# generic_victim.net
KiCad netlist of a schematic drawn in EAGLE
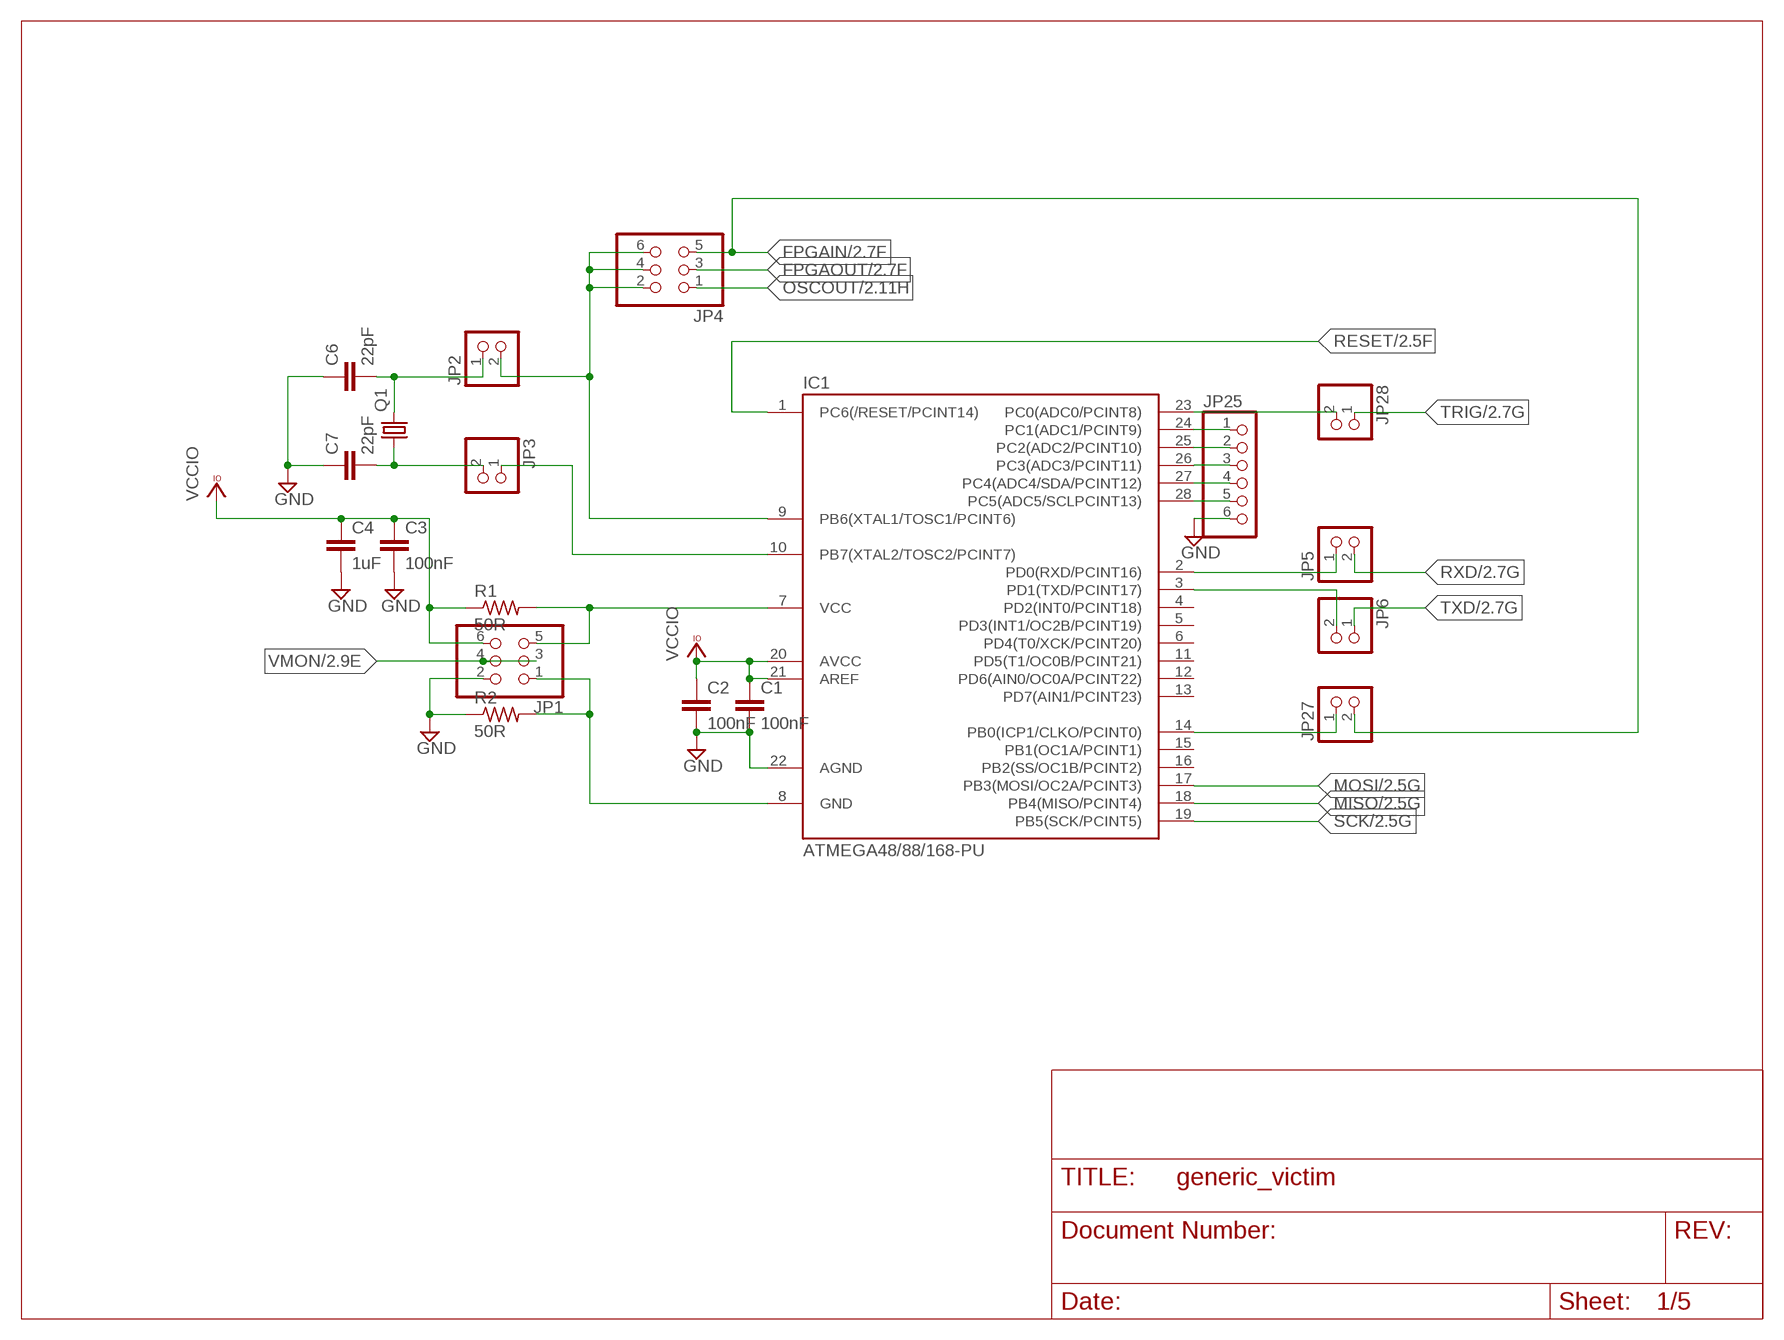
[diagram p0: schematic, sheet 1]
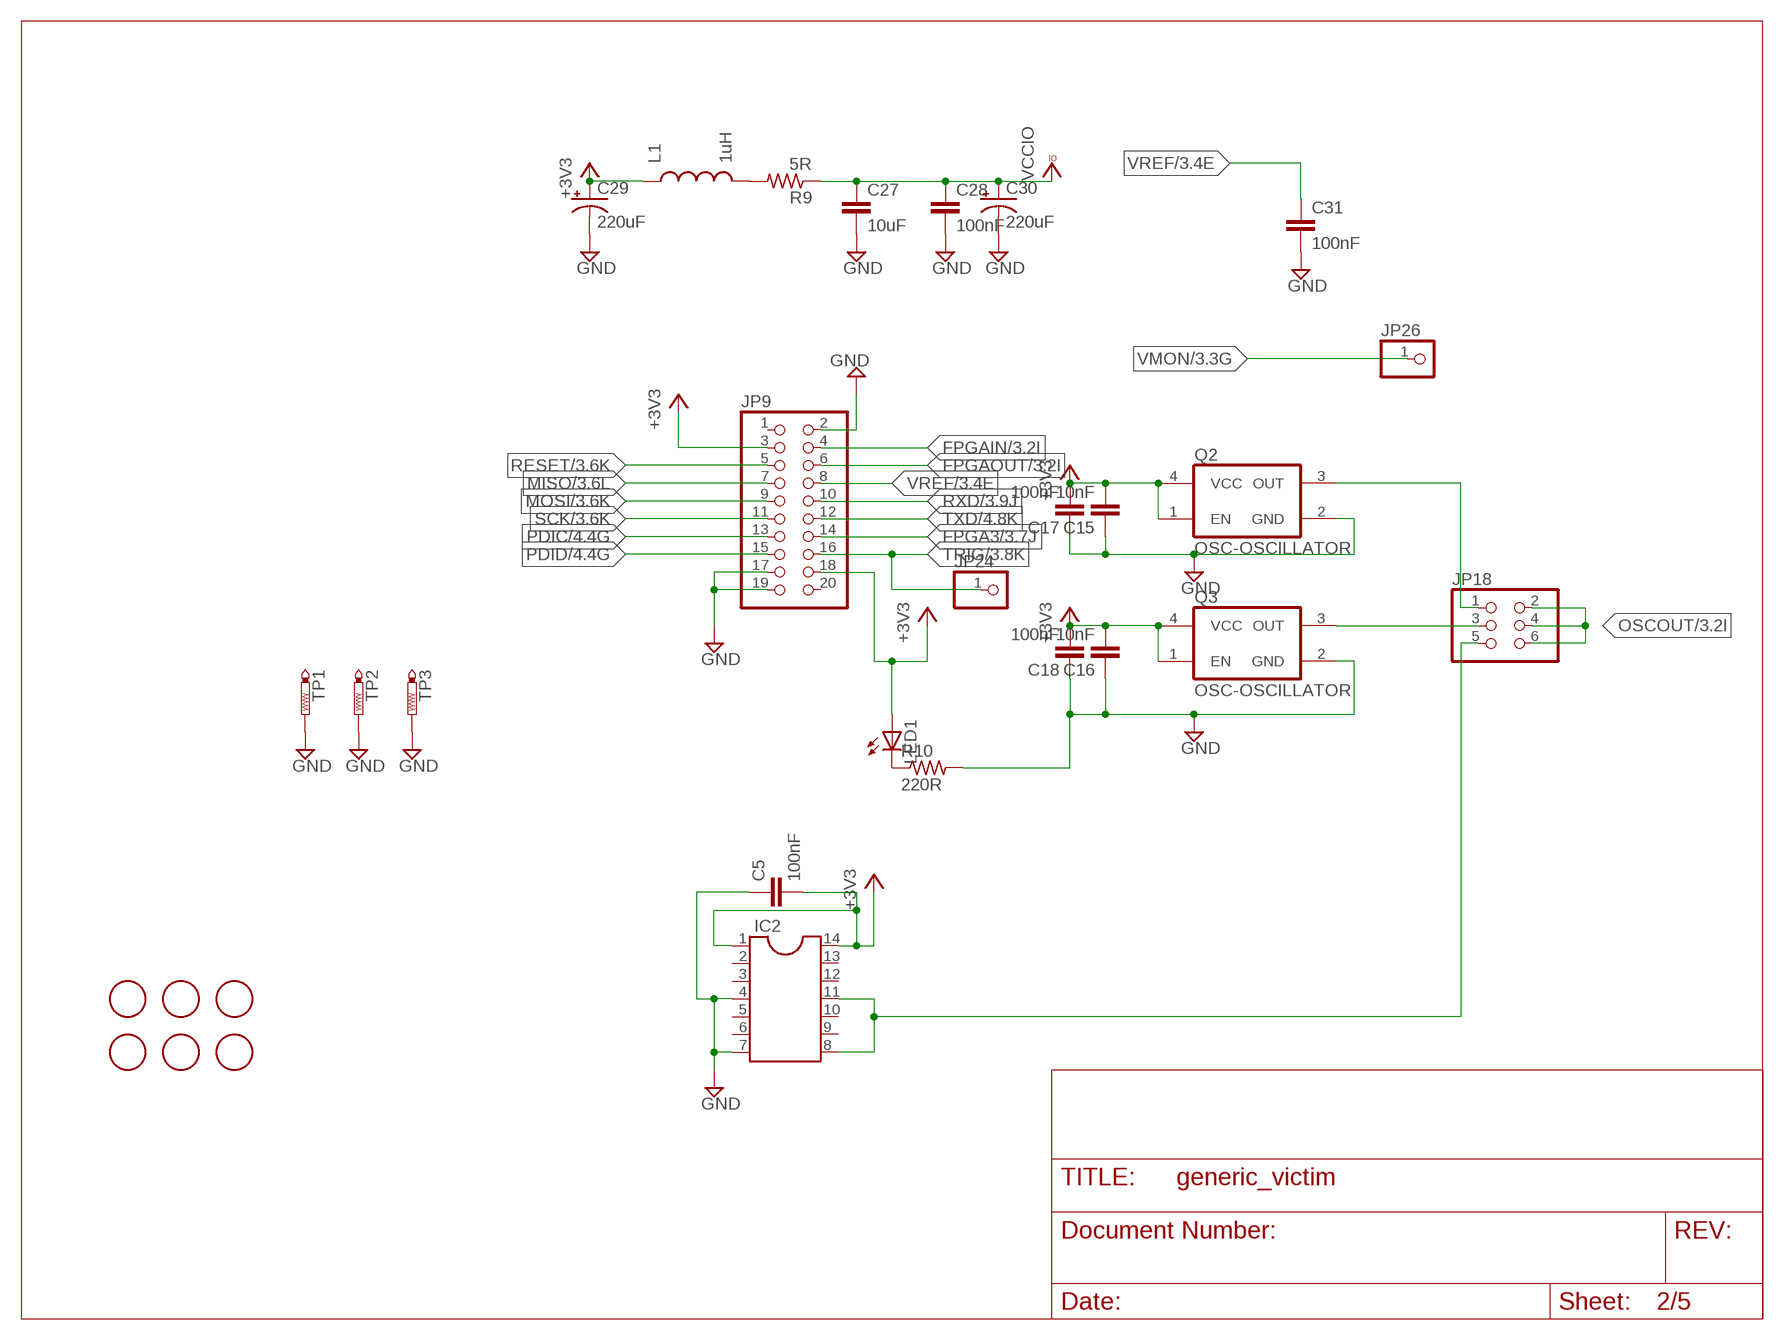
[diagram p1: schematic, sheet 2]
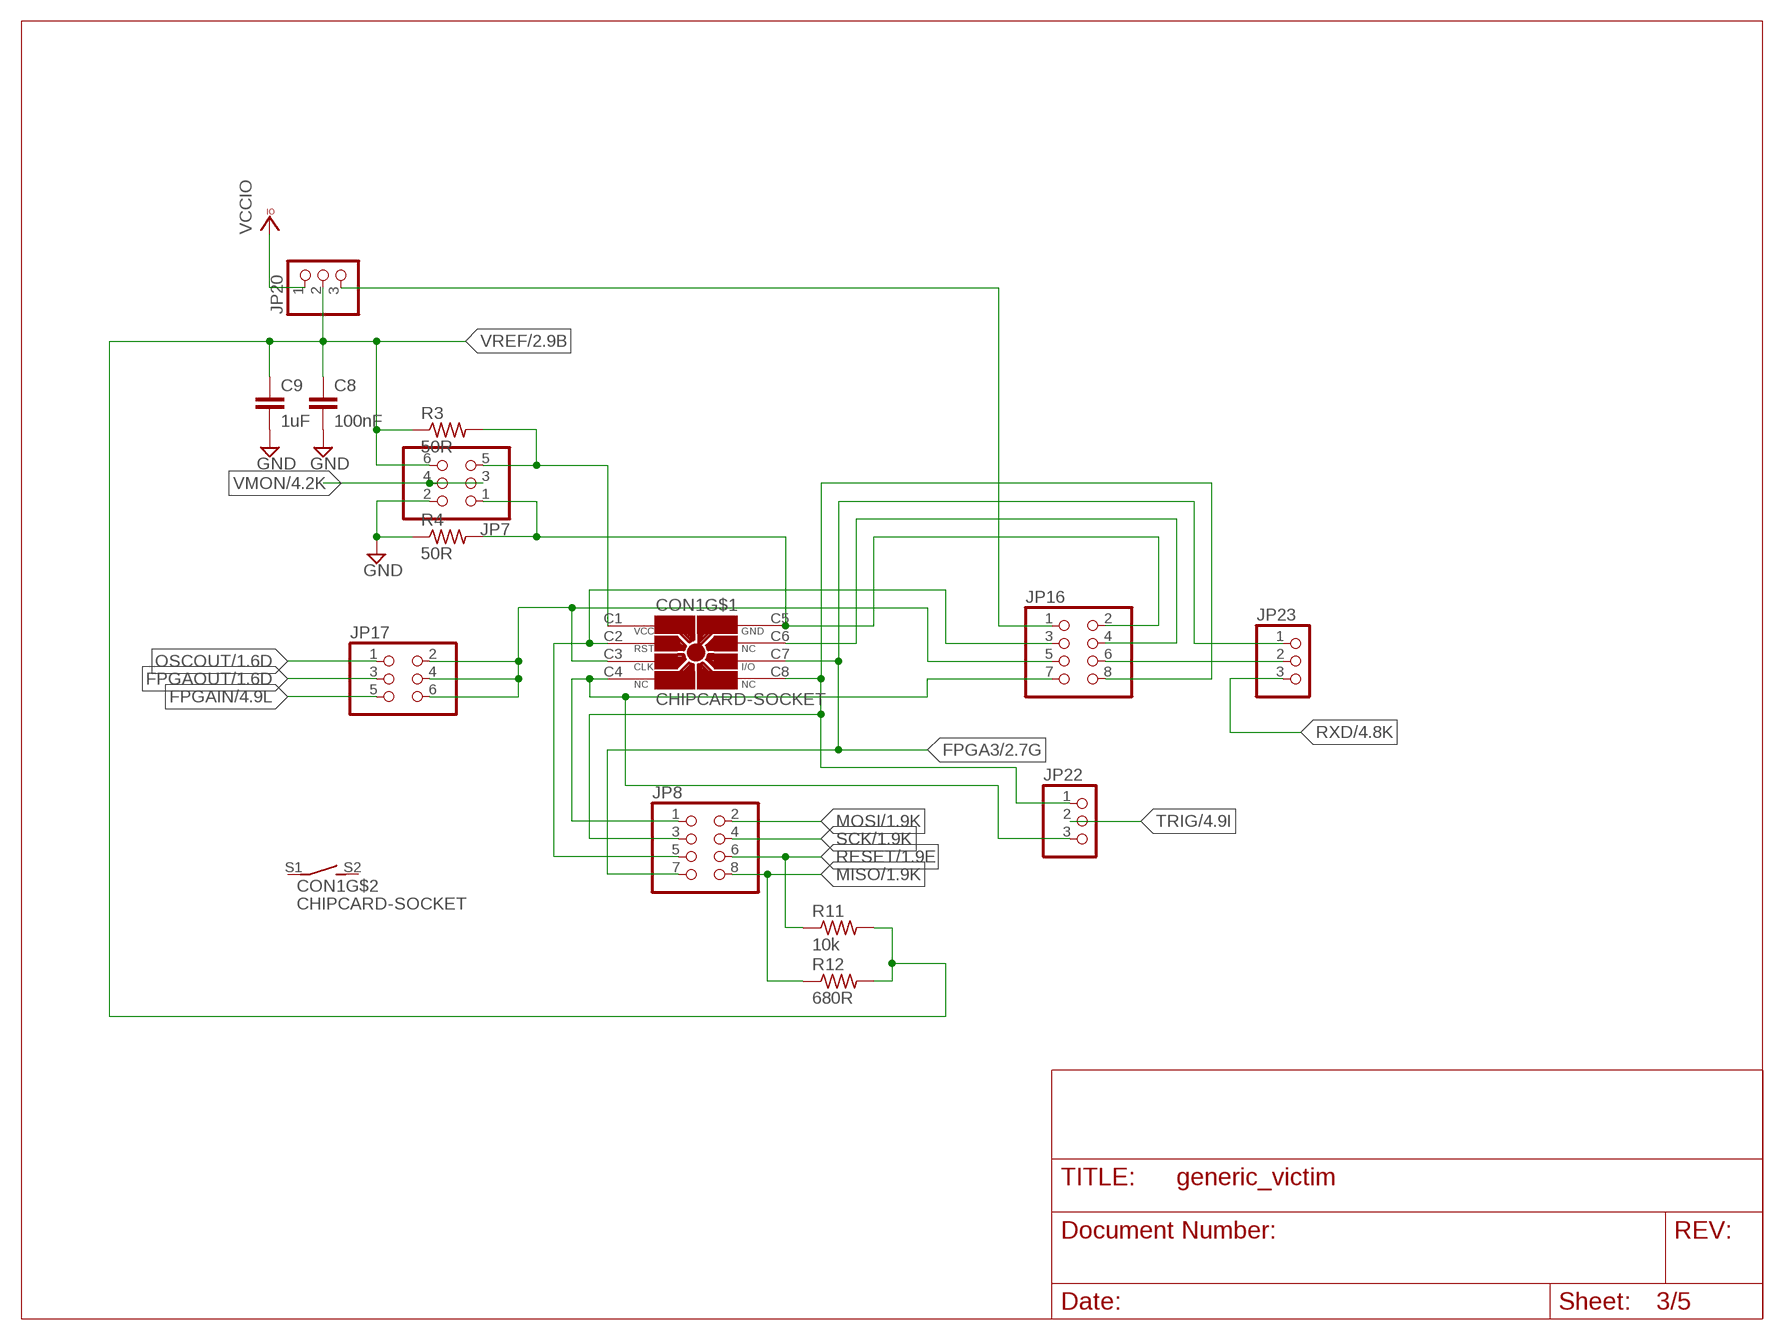
[diagram p2: schematic, sheet 3]
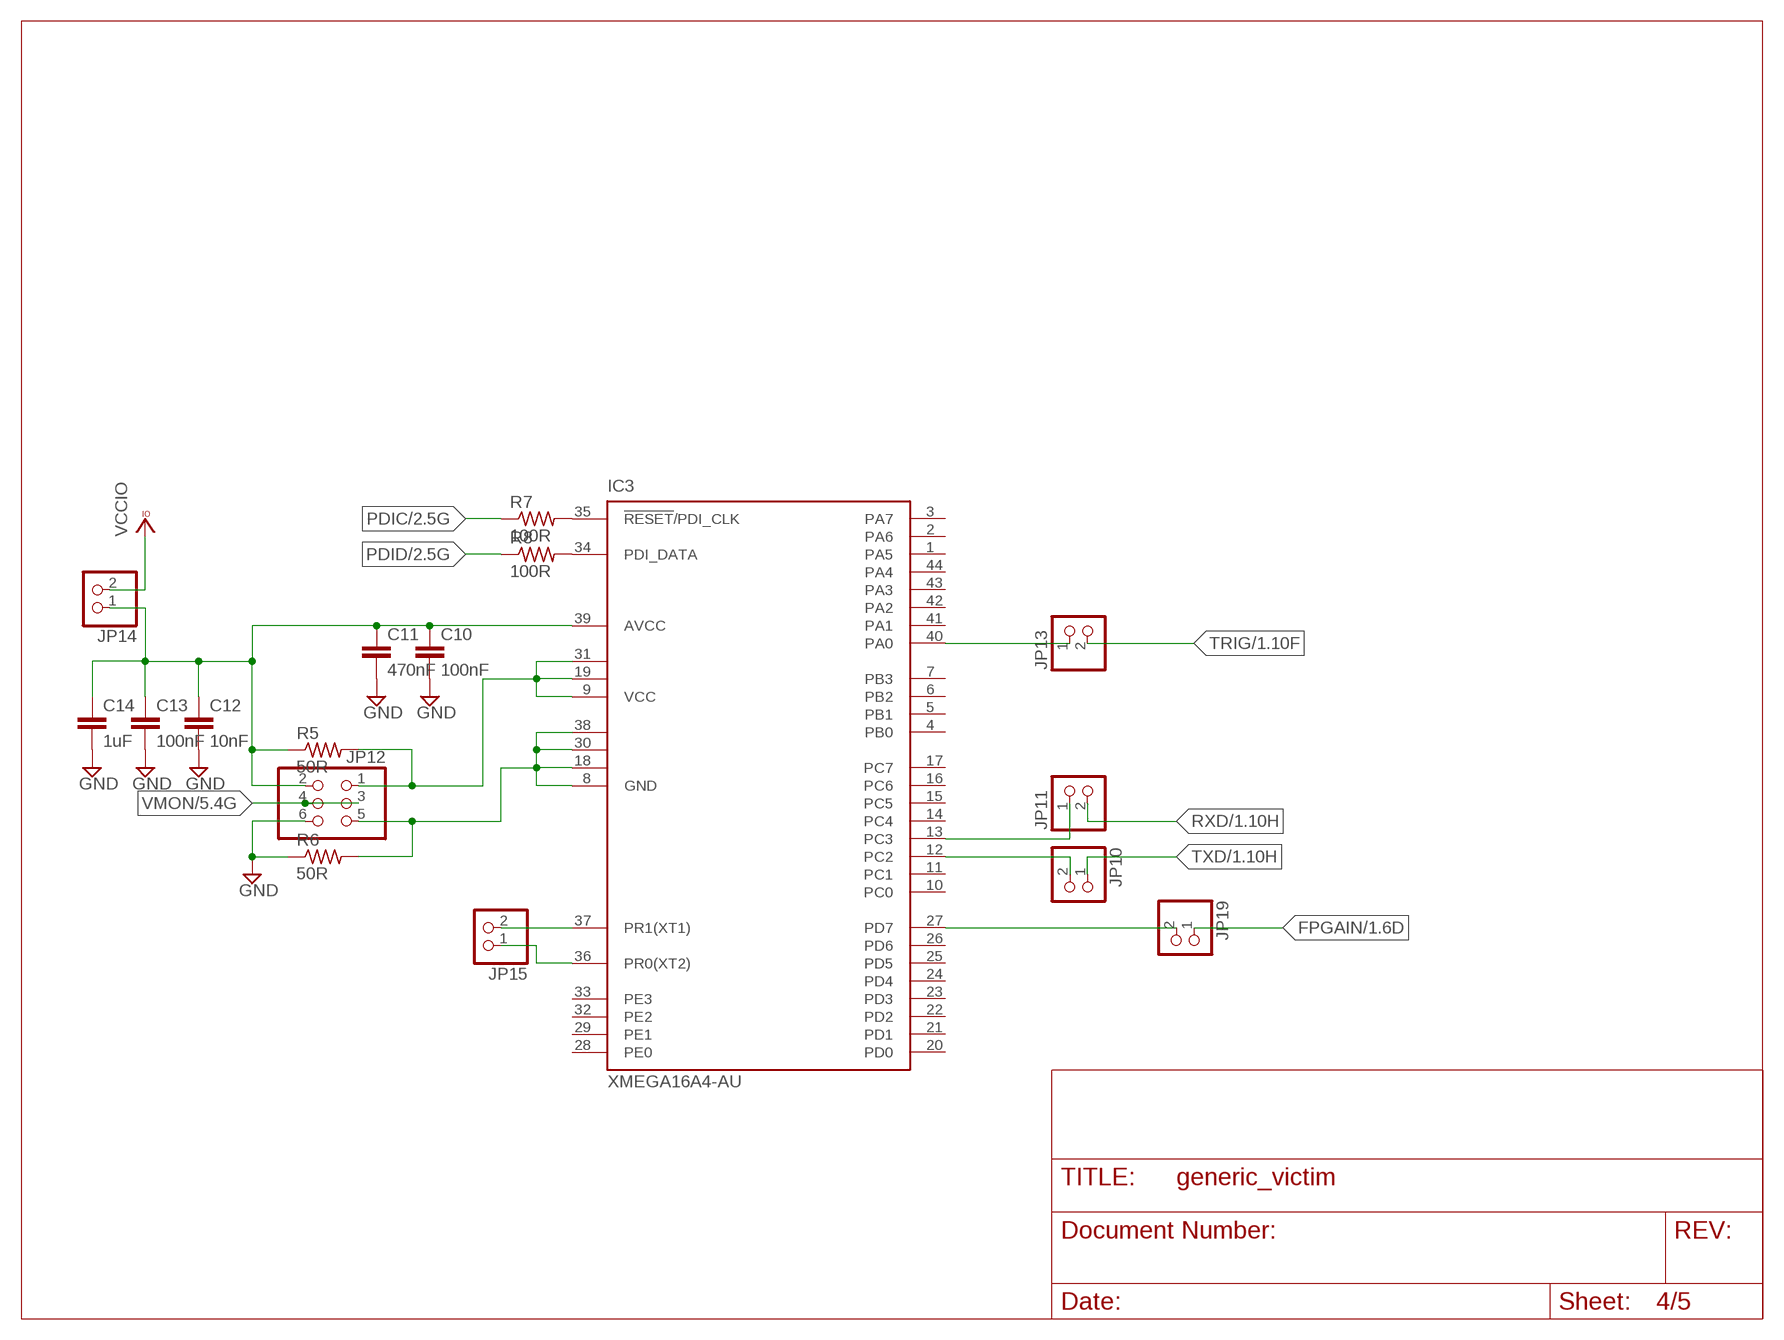
[diagram p3: schematic, sheet 4]
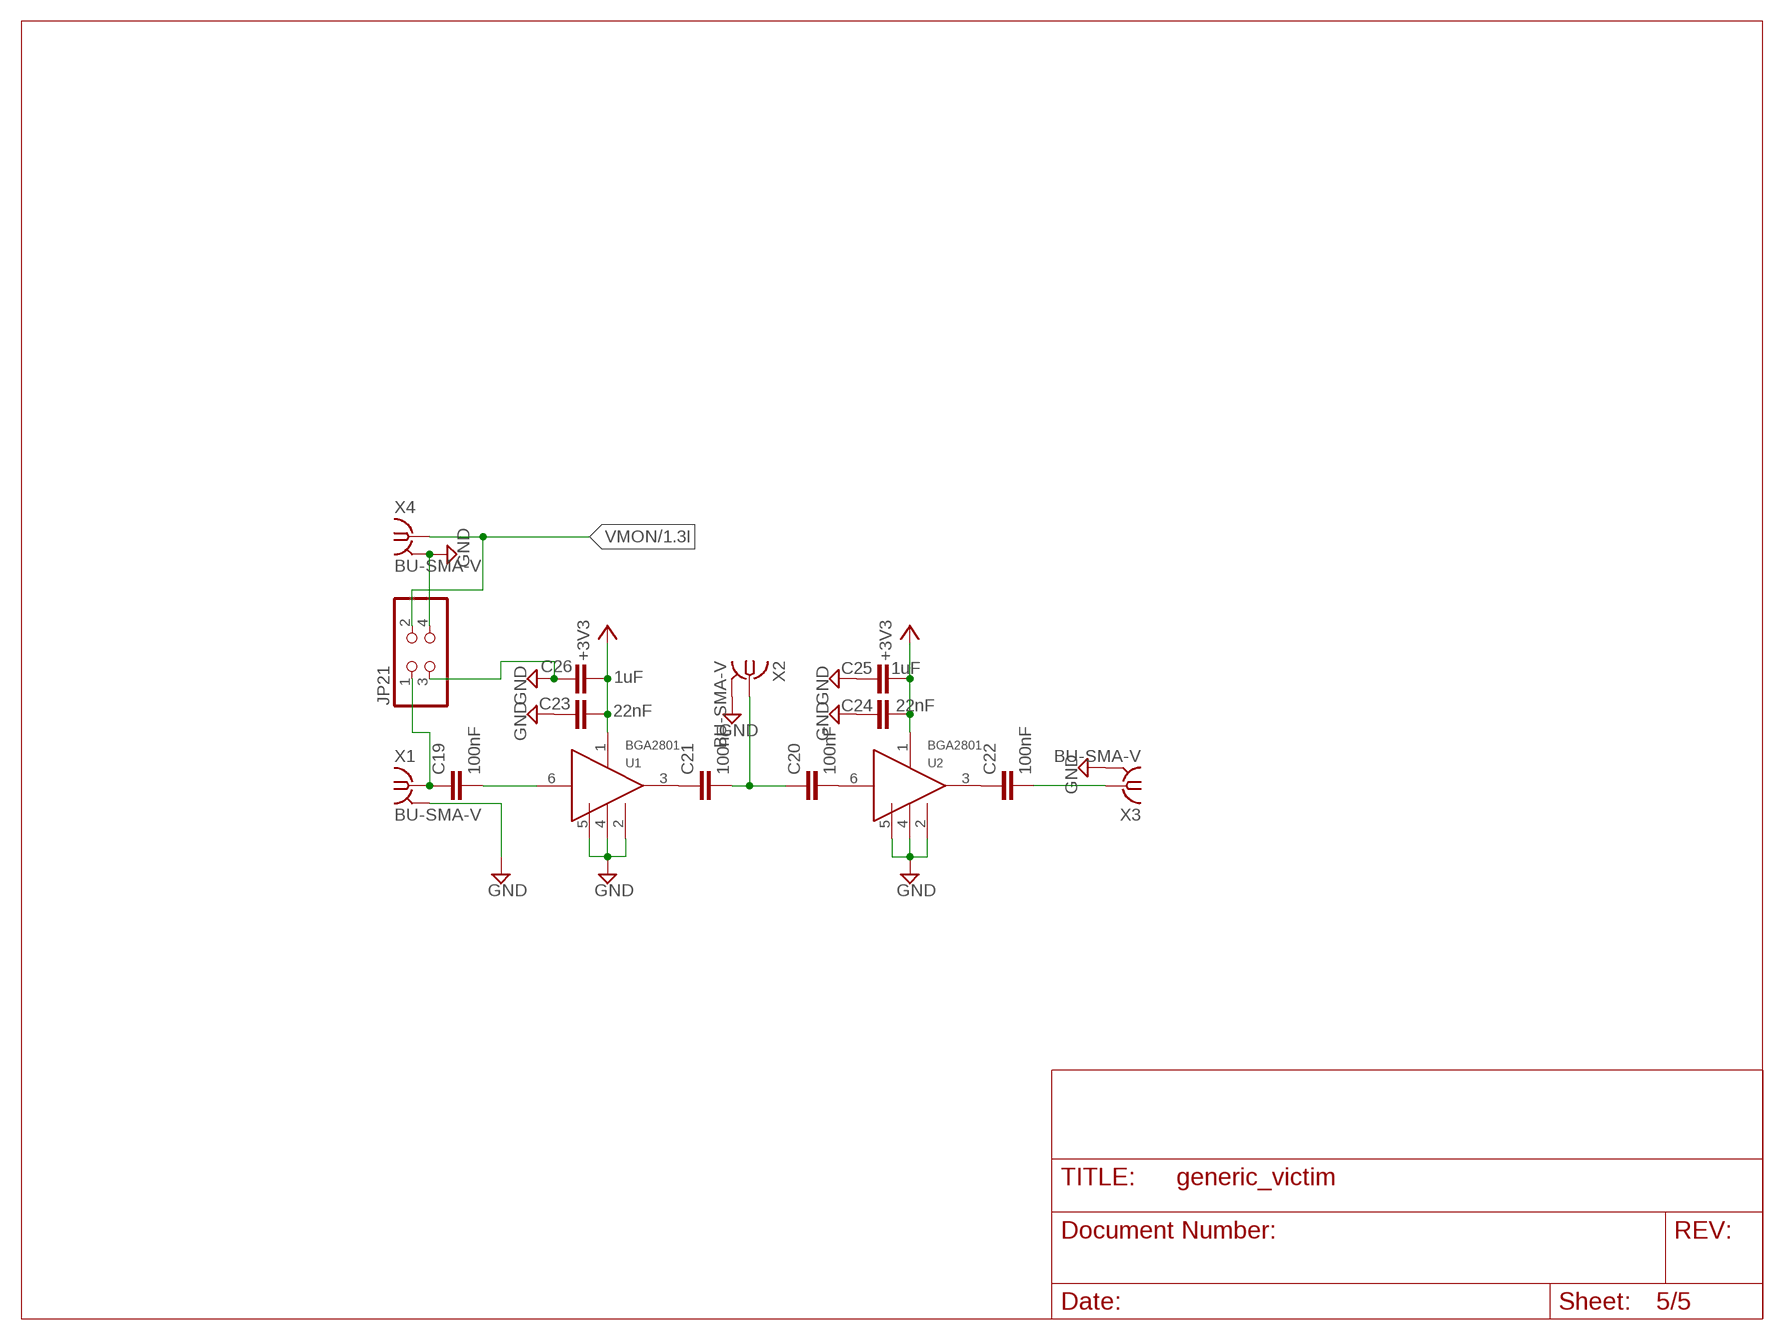
[diagram p4: schematic, sheet 5]

(export (version "E")
  (design (tool "Eeschema 10.0.6"))
  (components
    (comp (ref "C10")
      (value "100nF")
      (footprint "eagle-import:C0805")
      (libsource (lib "eagle-import") (part "resistor_C-EUC0805"))
    )
    (comp (ref "C11")
      (value "470nF")
      (footprint "eagle-import:C0805")
      (libsource (lib "eagle-import") (part "resistor_C-EUC0805"))
    )
    (comp (ref "C12")
      (value "10nF")
      (footprint "eagle-import:C0805")
      (libsource (lib "eagle-import") (part "resistor_C-EUC0805"))
    )
    (comp (ref "C13")
      (value "100nF")
      (footprint "eagle-import:C0805")
      (libsource (lib "eagle-import") (part "resistor_C-EUC0805"))
    )
    (comp (ref "C14")
      (value "1uF")
      (footprint "eagle-import:C0805")
      (libsource (lib "eagle-import") (part "resistor_C-EUC0805"))
    )
    (comp (ref "IC3")
      (value "XMEGA16A4-AU")
      (footprint "eagle-import:TQFP44")
      (libsource (lib "eagle-import") (part "XMEGA16A4A"))
    )
    (comp (ref "JP10")
      (value "PINHD-1X2")
      (footprint "eagle-import:1X02")
      (libsource (lib "eagle-import") (part "PINHD-1X2"))
    )
    (comp (ref "JP11")
      (value "PINHD-1X2")
      (footprint "eagle-import:1X02")
      (libsource (lib "eagle-import") (part "PINHD-1X2"))
    )
    (comp (ref "JP12")
      (value "PINHD-2X3")
      (footprint "eagle-import:2X03")
      (libsource (lib "eagle-import") (part "PINHD-2X3"))
    )
    (comp (ref "JP13")
      (value "PINHD-1X2")
      (footprint "eagle-import:1X02")
      (libsource (lib "eagle-import") (part "PINHD-1X2"))
    )
    (comp (ref "JP14")
      (value "PINHD-1X2")
      (footprint "eagle-import:1X02")
      (libsource (lib "eagle-import") (part "PINHD-1X2"))
    )
    (comp (ref "JP15")
      (value "PINHD-1X2")
      (footprint "eagle-import:1X02")
      (libsource (lib "eagle-import") (part "PINHD-1X2"))
    )
    (comp (ref "JP19")
      (value "PINHD-1X2")
      (footprint "eagle-import:1X02")
      (libsource (lib "eagle-import") (part "PINHD-1X2"))
    )
    (comp (ref "R5")
      (value "50R")
      (footprint "eagle-import:R0805")
      (libsource (lib "eagle-import") (part "resistor_R-US_R0805"))
    )
    (comp (ref "R6")
      (value "50R")
      (footprint "eagle-import:R0805")
      (libsource (lib "eagle-import") (part "resistor_R-US_R0805"))
    )
    (comp (ref "R7")
      (value "100R")
      (footprint "eagle-import:M0805")
      (libsource (lib "eagle-import") (part "resistor_R-US_M0805"))
    )
    (comp (ref "R8")
      (value "100R")
      (footprint "eagle-import:M0805")
      (libsource (lib "eagle-import") (part "resistor_R-US_M0805"))
    )
    (comp (ref "C5")
      (value "100nF")
      (footprint "eagle-import:C0805")
      (libsource (lib "eagle-import") (part "resistor_C-EUC0805"))
    )
    (comp (ref "C15")
      (value "10nF")
      (footprint "eagle-import:C0603")
      (libsource (lib "eagle-import") (part "resistor_C-EUC0603"))
    )
    (comp (ref "C16")
      (value "10nF")
      (footprint "eagle-import:C0603")
      (libsource (lib "eagle-import") (part "resistor_C-EUC0603"))
    )
    (comp (ref "C17")
      (value "100nF")
      (footprint "eagle-import:C0603")
      (libsource (lib "eagle-import") (part "resistor_C-EUC0603"))
    )
    (comp (ref "C18")
      (value "100nF")
      (footprint "eagle-import:C0603")
      (libsource (lib "eagle-import") (part "resistor_C-EUC0603"))
    )
    (comp (ref "C27")
      (value "10uF")
      (footprint "eagle-import:C0805")
      (libsource (lib "eagle-import") (part "C-EUC0805"))
    )
    (comp (ref "C28")
      (value "100nF")
      (footprint "eagle-import:C0805")
      (libsource (lib "eagle-import") (part "C-EUC0805"))
    )
    (comp (ref "C29")
      (value "220uF")
      (footprint "eagle-import:E3,5-8")
      (libsource (lib "eagle-import") (part "CPOL-USE3.5-8"))
    )
    (comp (ref "C30")
      (value "220uF")
      (footprint "eagle-import:E3,5-8")
      (libsource (lib "eagle-import") (part "CPOL-USE3.5-8"))
    )
    (comp (ref "C31")
      (value "100nF")
      (footprint "eagle-import:C0805")
      (libsource (lib "eagle-import") (part "C-EUC0805"))
    )
    (comp (ref "IC2")
      (value "DIL14S")
      (footprint "eagle-import:SOCKET-14")
      (libsource (lib "eagle-import") (part "DIL14S"))
    )
    (comp (ref "JP9")
      (value "PINHD-2X10")
      (footprint "eagle-import:2X10")
      (libsource (lib "eagle-import") (part "PINHD-2X10"))
    )
    (comp (ref "JP18")
      (value "PINHD-2X3")
      (footprint "eagle-import:2X03")
      (libsource (lib "eagle-import") (part "PINHD-2X3"))
    )
    (comp (ref "JP24")
      (value "PINHD-1X1")
      (footprint "eagle-import:1X01")
      (libsource (lib "eagle-import") (part "PINHD-1X1"))
    )
    (comp (ref "JP26")
      (value "PINHD-1X1")
      (footprint "eagle-import:1X01")
      (libsource (lib "eagle-import") (part "PINHD-1X1"))
    )
    (comp (ref "L1")
      (value "1uH")
      (footprint "eagle-import:0805")
      (libsource (lib "eagle-import") (part "INDUCTOR0805"))
    )
    (comp (ref "LED1")
      (value "LED3MM")
      (footprint "eagle-import:LED3MM")
      (libsource (lib "eagle-import") (part "LED3MM"))
    )
    (comp (ref "Q2")
      (value "OSC-OSCILLATOR")
      (footprint "eagle-import:OSCILLATOR_7X5_SMD")
      (libsource (lib "eagle-import") (part "OSC-OSCILLATOR"))
    )
    (comp (ref "Q3")
      (value "OSC-OSCILLATOR")
      (footprint "eagle-import:OSCILLATOR_7X5_SMD")
      (libsource (lib "eagle-import") (part "OSC-OSCILLATOR"))
    )
    (comp (ref "R9")
      (value "5R")
      (footprint "eagle-import:R0805")
      (libsource (lib "eagle-import") (part "R-US_R0805"))
    )
    (comp (ref "R10")
      (value "220R")
      (footprint "eagle-import:R0805")
      (libsource (lib "eagle-import") (part "resistor_R-US_R0805"))
    )
    (comp (ref "TP1")
      (value "PTR1PAD1-13")
      (footprint "eagle-import:P1-13")
      (libsource (lib "eagle-import") (part "PTR1PAD1-13"))
    )
    (comp (ref "TP2")
      (value "PTR1PAD1-13")
      (footprint "eagle-import:P1-13")
      (libsource (lib "eagle-import") (part "PTR1PAD1-13"))
    )
    (comp (ref "TP3")
      (value "PTR1PAD1-13")
      (footprint "eagle-import:P1-13")
      (libsource (lib "eagle-import") (part "PTR1PAD1-13"))
    )
    (comp (ref "U$1")
      (value "FIDUCIAL")
      (footprint "eagle-import:FIDUCIAL_1MM")
      (libsource (lib "eagle-import") (part "FIDUCIAL"))
    )
    (comp (ref "U$2")
      (value "FIDUCIAL")
      (footprint "eagle-import:FIDUCIAL_1MM")
      (libsource (lib "eagle-import") (part "FIDUCIAL"))
    )
    (comp (ref "U$3")
      (value "FIDUCIAL")
      (footprint "eagle-import:FIDUCIAL_1MM")
      (libsource (lib "eagle-import") (part "FIDUCIAL"))
    )
    (comp (ref "U$4")
      (value "FIDUCIAL")
      (footprint "eagle-import:FIDUCIAL_1MM")
      (libsource (lib "eagle-import") (part "FIDUCIAL"))
    )
    (comp (ref "U$5")
      (value "FIDUCIAL")
      (footprint "eagle-import:FIDUCIAL_1MM")
      (libsource (lib "eagle-import") (part "FIDUCIAL"))
    )
    (comp (ref "U$6")
      (value "FIDUCIAL")
      (footprint "eagle-import:FIDUCIAL_1MM")
      (libsource (lib "eagle-import") (part "FIDUCIAL"))
    )
    (comp (ref "C1")
      (value "100nF")
      (footprint "eagle-import:C0805")
      (libsource (lib "eagle-import") (part "resistor_C-EUC0805"))
    )
    (comp (ref "C2")
      (value "100nF")
      (footprint "eagle-import:C0805")
      (libsource (lib "eagle-import") (part "resistor_C-EUC0805"))
    )
    (comp (ref "C3")
      (value "100nF")
      (footprint "eagle-import:C0805")
      (libsource (lib "eagle-import") (part "resistor_C-EUC0805"))
    )
    (comp (ref "C4")
      (value "1uF")
      (footprint "eagle-import:C0805")
      (libsource (lib "eagle-import") (part "resistor_C-EUC0805"))
    )
    (comp (ref "C6")
      (value "22pF")
      (footprint "eagle-import:C0805")
      (libsource (lib "eagle-import") (part "resistor_C-EUC0805"))
    )
    (comp (ref "C7")
      (value "22pF")
      (footprint "eagle-import:C0805")
      (libsource (lib "eagle-import") (part "resistor_C-EUC0805"))
    )
    (comp (ref "IC1")
      (value "ATMEGA48/88/168-PU")
      (footprint "eagle-import:DIL28-3")
      (libsource (lib "eagle-import") (part "ATMEGA48/88/168-PU"))
    )
    (comp (ref "JP1")
      (value "PINHD-2X3")
      (footprint "eagle-import:2X03")
      (libsource (lib "eagle-import") (part "PINHD-2X3"))
    )
    (comp (ref "JP2")
      (value "PINHD-1X2")
      (footprint "eagle-import:1X02")
      (libsource (lib "eagle-import") (part "PINHD-1X2"))
    )
    (comp (ref "JP3")
      (value "PINHD-1X2")
      (footprint "eagle-import:1X02")
      (libsource (lib "eagle-import") (part "PINHD-1X2"))
    )
    (comp (ref "JP4")
      (value "PINHD-2X3")
      (footprint "eagle-import:2X03")
      (libsource (lib "eagle-import") (part "PINHD-2X3"))
    )
    (comp (ref "JP5")
      (value "PINHD-1X2")
      (footprint "eagle-import:1X02")
      (libsource (lib "eagle-import") (part "PINHD-1X2"))
    )
    (comp (ref "JP6")
      (value "PINHD-1X2")
      (footprint "eagle-import:1X02")
      (libsource (lib "eagle-import") (part "PINHD-1X2"))
    )
    (comp (ref "JP25")
      (value "PINHD-1X6")
      (footprint "eagle-import:1X06")
      (libsource (lib "eagle-import") (part "PINHD-1X6"))
    )
    (comp (ref "JP27")
      (value "PINHD-1X2")
      (footprint "eagle-import:1X02")
      (libsource (lib "eagle-import") (part "PINHD-1X2"))
    )
    (comp (ref "JP28")
      (value "PINHD-1X2")
      (footprint "eagle-import:1X02")
      (libsource (lib "eagle-import") (part "PINHD-1X2"))
    )
    (comp (ref "Q1")
      (value "CRYSTALHC49U70")
      (footprint "eagle-import:HC49U70")
      (libsource (lib "eagle-import") (part "CRYSTALHC49U70"))
    )
    (comp (ref "R1")
      (value "50R")
      (footprint "eagle-import:R0805")
      (libsource (lib "eagle-import") (part "resistor_R-US_R0805"))
    )
    (comp (ref "R2")
      (value "50R")
      (footprint "eagle-import:R0805")
      (libsource (lib "eagle-import") (part "resistor_R-US_R0805"))
    )
    (comp (ref "C19")
      (value "100nF")
      (footprint "eagle-import:C0603")
      (libsource (lib "eagle-import") (part "C-EUC0603"))
    )
    (comp (ref "C20")
      (value "100nF")
      (footprint "eagle-import:C0603")
      (libsource (lib "eagle-import") (part "C-EUC0603"))
    )
    (comp (ref "C21")
      (value "100nF")
      (footprint "eagle-import:C0603")
      (libsource (lib "eagle-import") (part "C-EUC0603"))
    )
    (comp (ref "C22")
      (value "100nF")
      (footprint "eagle-import:C0603")
      (libsource (lib "eagle-import") (part "C-EUC0603"))
    )
    (comp (ref "C23")
      (value "22nF")
      (footprint "eagle-import:C0603")
      (libsource (lib "eagle-import") (part "C-EUC0603"))
    )
    (comp (ref "C24")
      (value "22nF")
      (footprint "eagle-import:C0603")
      (libsource (lib "eagle-import") (part "C-EUC0603"))
    )
    (comp (ref "C25")
      (value "1uF")
      (footprint "eagle-import:C0603")
      (libsource (lib "eagle-import") (part "C-EUC0603"))
    )
    (comp (ref "C26")
      (value "1uF")
      (footprint "eagle-import:C0603")
      (libsource (lib "eagle-import") (part "C-EUC0603"))
    )
    (comp (ref "JP21")
      (value "PINHD-2X2")
      (footprint "eagle-import:2X02")
      (libsource (lib "eagle-import") (part "PINHD-2X2"))
    )
    (comp (ref "U1")
      (value "BGA2801")
      (footprint "eagle-import:SOTT323-6")
      (libsource (lib "eagle-import") (part "BGA2801"))
    )
    (comp (ref "U2")
      (value "BGA2801")
      (footprint "eagle-import:SOTT323-6")
      (libsource (lib "eagle-import") (part "BGA2801"))
    )
    (comp (ref "X1")
      (value "BU-SMA-V")
      (footprint "eagle-import:BU-SMA-V")
      (libsource (lib "eagle-import") (part "BU-SMA-V"))
    )
    (comp (ref "X2")
      (value "BU-SMA-V")
      (footprint "eagle-import:BU-SMA-V")
      (libsource (lib "eagle-import") (part "BU-SMA-V"))
    )
    (comp (ref "X3")
      (value "BU-SMA-V")
      (footprint "eagle-import:BU-SMA-V")
      (libsource (lib "eagle-import") (part "BU-SMA-V"))
    )
    (comp (ref "X4")
      (value "BU-SMA-V")
      (footprint "eagle-import:BU-SMA-V")
      (libsource (lib "eagle-import") (part "BU-SMA-V"))
    )
    (comp (ref "C8")
      (value "100nF")
      (footprint "eagle-import:C0805")
      (libsource (lib "eagle-import") (part "resistor_C-EUC0805"))
    )
    (comp (ref "C9")
      (value "1uF")
      (footprint "eagle-import:C0805")
      (libsource (lib "eagle-import") (part "resistor_C-EUC0805"))
    )
    (comp (ref "CON1")
      (value "CHIPCARD-SOCKET")
      (footprint "eagle-import:7334L2622F05LF")
      (libsource (lib "eagle-import") (part "CHIPCARD-SOCKET"))
    )
    (comp (ref "JP7")
      (value "PINHD-2X3")
      (footprint "eagle-import:2X03")
      (libsource (lib "eagle-import") (part "PINHD-2X3"))
    )
    (comp (ref "JP8")
      (value "PINHD-2X4")
      (footprint "eagle-import:2X04")
      (libsource (lib "eagle-import") (part "PINHD-2X4"))
    )
    (comp (ref "JP16")
      (value "PINHD-2X4")
      (footprint "eagle-import:2X04")
      (libsource (lib "eagle-import") (part "PINHD-2X4"))
    )
    (comp (ref "JP17")
      (value "PINHD-2X3")
      (footprint "eagle-import:2X03")
      (libsource (lib "eagle-import") (part "PINHD-2X3"))
    )
    (comp (ref "JP20")
      (value "PINHD-1X3")
      (footprint "eagle-import:1X03")
      (libsource (lib "eagle-import") (part "PINHD-1X3"))
    )
    (comp (ref "JP22")
      (value "PINHD-1X3")
      (footprint "eagle-import:1X03")
      (libsource (lib "eagle-import") (part "PINHD-1X3"))
    )
    (comp (ref "JP23")
      (value "PINHD-1X3")
      (footprint "eagle-import:1X03")
      (libsource (lib "eagle-import") (part "PINHD-1X3"))
    )
    (comp (ref "R3")
      (value "50R")
      (footprint "eagle-import:R0805")
      (libsource (lib "eagle-import") (part "resistor_R-US_R0805"))
    )
    (comp (ref "R4")
      (value "50R")
      (footprint "eagle-import:R0805")
      (libsource (lib "eagle-import") (part "resistor_R-US_R0805"))
    )
    (comp (ref "R11")
      (value "10k")
      (footprint "eagle-import:R0805")
      (libsource (lib "eagle-import") (part "resistor_R-US_R0805"))
    )
    (comp (ref "R12")
      (value "680R")
      (footprint "eagle-import:R0805")
      (libsource (lib "eagle-import") (part "resistor_R-US_R0805"))
    )
  )
  (nets
    (net (code "1") (name "+3V3") (class "Default")
      (node (ref "C15") (pin "2") (pinfunction "2_2") (pintype "passive"))
      (node (ref "C16") (pin "2") (pinfunction "2_2") (pintype "passive"))
      (node (ref "C17") (pin "2") (pinfunction "2_2") (pintype "passive"))
      (node (ref "C18") (pin "2") (pinfunction "2_2") (pintype "passive"))
      (node (ref "C23") (pin "2") (pinfunction "2_2") (pintype "passive"))
      (node (ref "C24") (pin "2") (pinfunction "2_2") (pintype "passive"))
      (node (ref "C25") (pin "2") (pinfunction "2_2") (pintype "passive"))
      (node (ref "C26") (pin "2") (pinfunction "2_2") (pintype "passive"))
      (node (ref "C29") (pin "+") (pinfunction "+_+") (pintype "passive"))
      (node (ref "C5") (pin "2") (pinfunction "2_2") (pintype "passive"))
      (node (ref "IC2") (pin "1") (pinfunction "1_1") (pintype "passive"))
      (node (ref "IC2") (pin "14") (pinfunction "14_14") (pintype "passive"))
      (node (ref "JP9") (pin "18") (pinfunction "18_18") (pintype "passive"))
      (node (ref "JP9") (pin "3") (pinfunction "3_3") (pintype "passive"))
      (node (ref "L1") (pin "1") (pinfunction "1_1") (pintype "passive"))
      (node (ref "LED1") (pin "A") (pinfunction "A_A") (pintype "passive"))
      (node (ref "Q2") (pin "1") (pinfunction "EN_1") (pintype "input"))
      (node (ref "Q2") (pin "4") (pinfunction "VCC_4") (pintype "power_in"))
      (node (ref "Q3") (pin "1") (pinfunction "EN_1") (pintype "input"))
      (node (ref "Q3") (pin "4") (pinfunction "VCC_4") (pintype "power_in"))
      (node (ref "U1") (pin "1") (pinfunction "VCC_1") (pintype "bidirectional"))
      (node (ref "U2") (pin "1") (pinfunction "VCC_1") (pintype "bidirectional"))
    )
    (net (code "2") (name "FPGA3") (class "Default")
      (node (ref "CON1") (pin "C7") (pinfunction "I/O_C7") (pintype "passive"))
      (node (ref "JP23") (pin "1") (pinfunction "1_1") (pintype "passive"))
      (node (ref "JP8") (pin "7") (pinfunction "7_7") (pintype "passive"))
      (node (ref "JP9") (pin "14") (pinfunction "14_14") (pintype "passive"))
    )
    (net (code "3") (name "FPGAIN") (class "Default")
      (node (ref "JP17") (pin "5") (pinfunction "5_5") (pintype "passive"))
      (node (ref "JP19") (pin "1") (pinfunction "1_1") (pintype "passive"))
      (node (ref "JP27") (pin "2") (pinfunction "2_2") (pintype "passive"))
      (node (ref "JP4") (pin "5") (pinfunction "5_5") (pintype "passive"))
      (node (ref "JP9") (pin "4") (pinfunction "4_4") (pintype "passive"))
    )
    (net (code "4") (name "FPGAOUT") (class "Default")
      (node (ref "JP17") (pin "3") (pinfunction "3_3") (pintype "passive"))
      (node (ref "JP4") (pin "3") (pinfunction "3_3") (pintype "passive"))
      (node (ref "JP9") (pin "6") (pinfunction "6_6") (pintype "passive"))
    )
    (net (code "5") (name "GND") (class "Default")
      (node (ref "C1") (pin "2") (pinfunction "2_2") (pintype "passive"))
      (node (ref "C10") (pin "2") (pinfunction "2_2") (pintype "passive"))
      (node (ref "C11") (pin "2") (pinfunction "2_2") (pintype "passive"))
      (node (ref "C12") (pin "2") (pinfunction "2_2") (pintype "passive"))
      (node (ref "C13") (pin "2") (pinfunction "2_2") (pintype "passive"))
      (node (ref "C14") (pin "2") (pinfunction "2_2") (pintype "passive"))
      (node (ref "C15") (pin "1") (pinfunction "1_1") (pintype "passive"))
      (node (ref "C16") (pin "1") (pinfunction "1_1") (pintype "passive"))
      (node (ref "C17") (pin "1") (pinfunction "1_1") (pintype "passive"))
      (node (ref "C18") (pin "1") (pinfunction "1_1") (pintype "passive"))
      (node (ref "C2") (pin "2") (pinfunction "2_2") (pintype "passive"))
      (node (ref "C23") (pin "1") (pinfunction "1_1") (pintype "passive"))
      (node (ref "C24") (pin "1") (pinfunction "1_1") (pintype "passive"))
      (node (ref "C25") (pin "1") (pinfunction "1_1") (pintype "passive"))
      (node (ref "C26") (pin "1") (pinfunction "1_1") (pintype "passive"))
      (node (ref "C27") (pin "2") (pinfunction "2_2") (pintype "passive"))
      (node (ref "C28") (pin "2") (pinfunction "2_2") (pintype "passive"))
      (node (ref "C29") (pin "-") (pinfunction "-_-") (pintype "passive"))
      (node (ref "C3") (pin "2") (pinfunction "2_2") (pintype "passive"))
      (node (ref "C30") (pin "-") (pinfunction "-_-") (pintype "passive"))
      (node (ref "C31") (pin "2") (pinfunction "2_2") (pintype "passive"))
      (node (ref "C4") (pin "2") (pinfunction "2_2") (pintype "passive"))
      (node (ref "C5") (pin "1") (pinfunction "1_1") (pintype "passive"))
      (node (ref "C6") (pin "1") (pinfunction "1_1") (pintype "passive"))
      (node (ref "C7") (pin "1") (pinfunction "1_1") (pintype "passive"))
      (node (ref "C8") (pin "2") (pinfunction "2_2") (pintype "passive"))
      (node (ref "C9") (pin "2") (pinfunction "2_2") (pintype "passive"))
      (node (ref "IC1") (pin "22") (pinfunction "AGND_22") (pintype "power_in"))
      (node (ref "IC2") (pin "4") (pinfunction "4_4") (pintype "passive"))
      (node (ref "IC2") (pin "7") (pinfunction "7_7") (pintype "passive"))
      (node (ref "JP1") (pin "2") (pinfunction "2_2") (pintype "passive"))
      (node (ref "JP12") (pin "6") (pinfunction "6_6") (pintype "passive"))
      (node (ref "JP21") (pin "3") (pinfunction "3_3") (pintype "passive"))
      (node (ref "JP21") (pin "4") (pinfunction "4_4") (pintype "passive"))
      (node (ref "JP25") (pin "6") (pinfunction "6_6") (pintype "passive"))
      (node (ref "JP7") (pin "2") (pinfunction "2_2") (pintype "passive"))
      (node (ref "JP9") (pin "17") (pinfunction "17_17") (pintype "passive"))
      (node (ref "JP9") (pin "19") (pinfunction "19_19") (pintype "passive"))
      (node (ref "JP9") (pin "2") (pinfunction "2_2") (pintype "passive"))
      (node (ref "Q2") (pin "2") (pinfunction "GND_2") (pintype "power_in"))
      (node (ref "Q3") (pin "2") (pinfunction "GND_2") (pintype "power_in"))
      (node (ref "R10") (pin "2") (pinfunction "2_2") (pintype "passive"))
      (node (ref "R2") (pin "1") (pinfunction "1_1") (pintype "passive"))
      (node (ref "R4") (pin "1") (pinfunction "1_1") (pintype "passive"))
      (node (ref "R6") (pin "1") (pinfunction "1_1") (pintype "passive"))
      (node (ref "TP1") (pin "TP") (pinfunction "TP_TP") (pintype "input"))
      (node (ref "TP2") (pin "TP") (pinfunction "TP_TP") (pintype "input"))
      (node (ref "TP3") (pin "TP") (pinfunction "TP_TP") (pintype "input"))
      (node (ref "U1") (pin "2") (pinfunction "GND_2") (pintype "bidirectional"))
      (node (ref "U1") (pin "4") (pinfunction "GND_4") (pintype "bidirectional"))
      (node (ref "U1") (pin "5") (pinfunction "GND_5") (pintype "bidirectional"))
      (node (ref "U2") (pin "2") (pinfunction "GND_2") (pintype "bidirectional"))
      (node (ref "U2") (pin "4") (pinfunction "GND_4") (pintype "bidirectional"))
      (node (ref "U2") (pin "5") (pinfunction "GND_5") (pintype "bidirectional"))
      (node (ref "X1") (pin "2") (pinfunction "2_2") (pintype "passive"))
      (node (ref "X1") (pin "3") (pinfunction "2_3") (pintype "passive"))
      (node (ref "X1") (pin "4") (pinfunction "2_4") (pintype "passive"))
      (node (ref "X1") (pin "5") (pinfunction "2_5") (pintype "passive"))
      (node (ref "X2") (pin "2") (pinfunction "2_2") (pintype "passive"))
      (node (ref "X2") (pin "3") (pinfunction "2_3") (pintype "passive"))
      (node (ref "X2") (pin "4") (pinfunction "2_4") (pintype "passive"))
      (node (ref "X2") (pin "5") (pinfunction "2_5") (pintype "passive"))
      (node (ref "X3") (pin "2") (pinfunction "2_2") (pintype "passive"))
      (node (ref "X3") (pin "3") (pinfunction "2_3") (pintype "passive"))
      (node (ref "X3") (pin "4") (pinfunction "2_4") (pintype "passive"))
      (node (ref "X3") (pin "5") (pinfunction "2_5") (pintype "passive"))
      (node (ref "X4") (pin "2") (pinfunction "2_2") (pintype "passive"))
      (node (ref "X4") (pin "3") (pinfunction "2_3") (pintype "passive"))
      (node (ref "X4") (pin "4") (pinfunction "2_4") (pintype "passive"))
      (node (ref "X4") (pin "5") (pinfunction "2_5") (pintype "passive"))
    )
    (net (code "6") (name "MISO") (class "Default")
      (node (ref "IC1") (pin "18") (pinfunction "PB4(MISO/PCINT4)_18") (pintype "bidirectional"))
      (node (ref "JP8") (pin "8") (pinfunction "8_8") (pintype "passive"))
      (node (ref "JP9") (pin "7") (pinfunction "7_7") (pintype "passive"))
      (node (ref "R12") (pin "1") (pinfunction "1_1") (pintype "passive"))
    )
    (net (code "7") (name "MOSI") (class "Default")
      (node (ref "IC1") (pin "17") (pinfunction "PB3(MOSI/OC2A/PCINT3)_17") (pintype "bidirectional"))
      (node (ref "JP8") (pin "2") (pinfunction "2_2") (pintype "passive"))
      (node (ref "JP9") (pin "9") (pinfunction "9_9") (pintype "passive"))
    )
    (net (code "8") (name "Net-(C6-Pad2)") (class "Default")
      (node (ref "C6") (pin "2") (pinfunction "2_2") (pintype "passive"))
      (node (ref "JP2") (pin "1") (pinfunction "1_1") (pintype "passive"))
      (node (ref "Q1") (pin "2") (pinfunction "2_2") (pintype "passive"))
    )
    (net (code "9") (name "Net-(C7-Pad2)") (class "Default")
      (node (ref "C7") (pin "2") (pinfunction "2_2") (pintype "passive"))
      (node (ref "JP3") (pin "2") (pinfunction "2_2") (pintype "passive"))
      (node (ref "Q1") (pin "1") (pinfunction "1_1") (pintype "passive"))
    )
    (net (code "10") (name "Net-(C19-Pad1)") (class "Default")
      (node (ref "C19") (pin "1") (pinfunction "1_1") (pintype "passive"))
      (node (ref "JP21") (pin "1") (pinfunction "1_1") (pintype "passive"))
      (node (ref "X1") (pin "1") (pinfunction "1_1") (pintype "passive"))
    )
    (net (code "11") (name "Net-(C20-Pad1)") (class "Default")
      (node (ref "C20") (pin "1") (pinfunction "1_1") (pintype "passive"))
      (node (ref "C21") (pin "2") (pinfunction "2_2") (pintype "passive"))
      (node (ref "X2") (pin "1") (pinfunction "1_1") (pintype "passive"))
    )
    (net (code "12") (name "Net-(C22-Pad2)") (class "Default")
      (node (ref "C22") (pin "2") (pinfunction "2_2") (pintype "passive"))
      (node (ref "X3") (pin "1") (pinfunction "1_1") (pintype "passive"))
    )
    (net (code "13") (name "Net-(CON1A-CLK)") (class "Default")
      (node (ref "CON1") (pin "C3") (pinfunction "CLK_C3") (pintype "passive"))
      (node (ref "JP16") (pin "5") (pinfunction "5_5") (pintype "passive"))
      (node (ref "JP17") (pin "2") (pinfunction "2_2") (pintype "passive"))
      (node (ref "JP17") (pin "4") (pinfunction "4_4") (pintype "passive"))
      (node (ref "JP17") (pin "6") (pinfunction "6_6") (pintype "passive"))
    )
    (net (code "14") (name "Net-(CON1A-GND)") (class "Default")
      (node (ref "CON1") (pin "C5") (pinfunction "GND_C5") (pintype "passive"))
      (node (ref "JP16") (pin "2") (pinfunction "2_2") (pintype "passive"))
      (node (ref "JP7") (pin "1") (pinfunction "1_1") (pintype "passive"))
      (node (ref "R4") (pin "2") (pinfunction "2_2") (pintype "passive"))
    )
    (net (code "15") (name "Net-(CON1A-NC-PadC4)") (class "Default")
      (node (ref "CON1") (pin "C4") (pinfunction "NC_C4") (pintype "passive"))
      (node (ref "JP16") (pin "7") (pinfunction "7_7") (pintype "passive"))
      (node (ref "JP22") (pin "3") (pinfunction "3_3") (pintype "passive"))
      (node (ref "JP8") (pin "1") (pinfunction "1_1") (pintype "passive"))
    )
    (net (code "16") (name "Net-(CON1A-NC-PadC6)") (class "Default")
      (node (ref "CON1") (pin "C6") (pinfunction "NC_C6") (pintype "passive"))
      (node (ref "JP16") (pin "4") (pinfunction "4_4") (pintype "passive"))
    )
    (net (code "17") (name "Net-(CON1A-NC-PadC8)") (class "Default")
      (node (ref "CON1") (pin "C8") (pinfunction "NC_C8") (pintype "passive"))
      (node (ref "JP16") (pin "8") (pinfunction "8_8") (pintype "passive"))
      (node (ref "JP22") (pin "1") (pinfunction "1_1") (pintype "passive"))
      (node (ref "JP8") (pin "3") (pinfunction "3_3") (pintype "passive"))
    )
    (net (code "18") (name "Net-(CON1A-RST)") (class "Default")
      (node (ref "CON1") (pin "C2") (pinfunction "RST_C2") (pintype "passive"))
      (node (ref "JP16") (pin "3") (pinfunction "3_3") (pintype "passive"))
      (node (ref "JP8") (pin "5") (pinfunction "5_5") (pintype "passive"))
    )
    (net (code "19") (name "Net-(CON1A-VCC)") (class "Default")
      (node (ref "CON1") (pin "C1") (pinfunction "VCC_C1") (pintype "passive"))
      (node (ref "JP7") (pin "5") (pinfunction "5_5") (pintype "passive"))
      (node (ref "R3") (pin "2") (pinfunction "2_2") (pintype "passive"))
    )
    (net (code "20") (name "Net-(IC1-GND)") (class "Default")
      (node (ref "IC1") (pin "8") (pinfunction "GND_8") (pintype "power_in"))
      (node (ref "JP1") (pin "1") (pinfunction "1_1") (pintype "passive"))
      (node (ref "R2") (pin "2") (pinfunction "2_2") (pintype "passive"))
    )
    (net (code "21") (name "Net-(IC1-PB0(ICP1{slash}CLKO{slash}PCINT0))") (class "Default")
      (node (ref "IC1") (pin "14") (pinfunction "PB0(ICP1/CLKO/PCINT0)_14") (pintype "bidirectional"))
      (node (ref "JP27") (pin "1") (pinfunction "1_1") (pintype "passive"))
    )
    (net (code "22") (name "Net-(IC1-PB6(XTAL1{slash}TOSC1{slash}PCINT6))") (class "Default")
      (node (ref "IC1") (pin "9") (pinfunction "PB6(XTAL1/TOSC1/PCINT6)_9") (pintype "bidirectional"))
      (node (ref "JP2") (pin "2") (pinfunction "2_2") (pintype "passive"))
      (node (ref "JP4") (pin "2") (pinfunction "2_2") (pintype "passive"))
      (node (ref "JP4") (pin "4") (pinfunction "4_4") (pintype "passive"))
      (node (ref "JP4") (pin "6") (pinfunction "6_6") (pintype "passive"))
    )
    (net (code "23") (name "Net-(IC1-PB7(XTAL2{slash}TOSC2{slash}PCINT7))") (class "Default")
      (node (ref "IC1") (pin "10") (pinfunction "PB7(XTAL2/TOSC2/PCINT7)_10") (pintype "bidirectional"))
      (node (ref "JP3") (pin "1") (pinfunction "1_1") (pintype "passive"))
    )
    (net (code "24") (name "Net-(IC1-PC0(ADC0{slash}PCINT8))") (class "Default")
      (node (ref "IC1") (pin "23") (pinfunction "PC0(ADC0/PCINT8)_23") (pintype "bidirectional"))
      (node (ref "JP28") (pin "2") (pinfunction "2_2") (pintype "passive"))
    )
    (net (code "25") (name "Net-(IC1-PC1(ADC1{slash}PCINT9))") (class "Default")
      (node (ref "IC1") (pin "24") (pinfunction "PC1(ADC1/PCINT9)_24") (pintype "bidirectional"))
      (node (ref "JP25") (pin "1") (pinfunction "1_1") (pintype "passive"))
    )
    (net (code "26") (name "Net-(IC1-PC2(ADC2{slash}PCINT10))") (class "Default")
      (node (ref "IC1") (pin "25") (pinfunction "PC2(ADC2/PCINT10)_25") (pintype "bidirectional"))
      (node (ref "JP25") (pin "2") (pinfunction "2_2") (pintype "passive"))
    )
    (net (code "27") (name "Net-(IC1-PC3(ADC3{slash}PCINT11))") (class "Default")
      (node (ref "IC1") (pin "26") (pinfunction "PC3(ADC3/PCINT11)_26") (pintype "bidirectional"))
      (node (ref "JP25") (pin "3") (pinfunction "3_3") (pintype "passive"))
    )
    (net (code "28") (name "Net-(IC1-PC4(ADC4{slash}SDA{slash}PCINT12))") (class "Default")
      (node (ref "IC1") (pin "27") (pinfunction "PC4(ADC4/SDA/PCINT12)_27") (pintype "bidirectional"))
      (node (ref "JP25") (pin "4") (pinfunction "4_4") (pintype "passive"))
    )
    (net (code "29") (name "Net-(IC1-PC5(ADC5{slash}SCLPCINT13))") (class "Default")
      (node (ref "IC1") (pin "28") (pinfunction "PC5(ADC5/SCLPCINT13)_28") (pintype "bidirectional"))
      (node (ref "JP25") (pin "5") (pinfunction "5_5") (pintype "passive"))
    )
    (net (code "30") (name "Net-(IC1-PD0(RXD{slash}PCINT16))") (class "Default")
      (node (ref "IC1") (pin "2") (pinfunction "PD0(RXD/PCINT16)_2") (pintype "bidirectional"))
      (node (ref "JP5") (pin "1") (pinfunction "1_1") (pintype "passive"))
    )
    (net (code "31") (name "Net-(IC1-PD1(TXD{slash}PCINT17))") (class "Default")
      (node (ref "IC1") (pin "3") (pinfunction "PD1(TXD/PCINT17)_3") (pintype "bidirectional"))
      (node (ref "JP6") (pin "2") (pinfunction "2_2") (pintype "passive"))
    )
    (net (code "32") (name "Net-(IC1-VCC)") (class "Default")
      (node (ref "IC1") (pin "7") (pinfunction "VCC_7") (pintype "power_in"))
      (node (ref "JP1") (pin "5") (pinfunction "5_5") (pintype "passive"))
      (node (ref "R1") (pin "2") (pinfunction "2_2") (pintype "passive"))
    )
    (net (code "33") (name "Net-(IC2-Pad11)") (class "Default")
      (node (ref "IC2") (pin "11") (pinfunction "11_11") (pintype "passive"))
      (node (ref "IC2") (pin "8") (pinfunction "8_8") (pintype "passive"))
      (node (ref "JP18") (pin "5") (pinfunction "5_5") (pintype "passive"))
    )
    (net (code "34") (name "Net-(IC3-AVCC)") (class "Default")
      (node (ref "C10") (pin "1") (pinfunction "1_1") (pintype "passive"))
      (node (ref "C11") (pin "1") (pinfunction "1_1") (pintype "passive"))
      (node (ref "C12") (pin "1") (pinfunction "1_1") (pintype "passive"))
      (node (ref "C13") (pin "1") (pinfunction "1_1") (pintype "passive"))
      (node (ref "C14") (pin "1") (pinfunction "1_1") (pintype "passive"))
      (node (ref "IC3") (pin "39") (pinfunction "AVCC_39") (pintype "power_in"))
      (node (ref "JP12") (pin "2") (pinfunction "2_2") (pintype "passive"))
      (node (ref "JP14") (pin "1") (pinfunction "1_1") (pintype "passive"))
      (node (ref "R5") (pin "1") (pinfunction "1_1") (pintype "passive"))
    )
    (net (code "35") (name "Net-(IC3-GND)") (class "Default")
      (node (ref "IC3") (pin "18") (pinfunction "GND1_18") (pintype "power_in"))
      (node (ref "IC3") (pin "30") (pinfunction "GND2_30") (pintype "power_in"))
      (node (ref "IC3") (pin "38") (pinfunction "GND3_38") (pintype "power_in"))
      (node (ref "IC3") (pin "8") (pinfunction "GND_8") (pintype "power_in"))
      (node (ref "JP12") (pin "5") (pinfunction "5_5") (pintype "passive"))
      (node (ref "R6") (pin "2") (pinfunction "2_2") (pintype "passive"))
    )
    (net (code "36") (name "Net-(IC3-PA0)") (class "Default")
      (node (ref "IC3") (pin "40") (pinfunction "PA0_40") (pintype "bidirectional"))
      (node (ref "JP13") (pin "1") (pinfunction "1_1") (pintype "passive"))
    )
    (net (code "37") (name "Net-(IC3-PC2)") (class "Default")
      (node (ref "IC3") (pin "12") (pinfunction "PC2_12") (pintype "bidirectional"))
      (node (ref "JP10") (pin "2") (pinfunction "2_2") (pintype "passive"))
    )
    (net (code "38") (name "Net-(IC3-PC3)") (class "Default")
      (node (ref "IC3") (pin "13") (pinfunction "PC3_13") (pintype "bidirectional"))
      (node (ref "JP11") (pin "1") (pinfunction "1_1") (pintype "passive"))
    )
    (net (code "39") (name "Net-(IC3-PD7)") (class "Default")
      (node (ref "IC3") (pin "27") (pinfunction "PD7_27") (pintype "bidirectional"))
      (node (ref "JP19") (pin "2") (pinfunction "2_2") (pintype "passive"))
    )
    (net (code "40") (name "Net-(IC3-PDI_DATA)") (class "Default")
      (node (ref "IC3") (pin "34") (pinfunction "PDI_DATA_34") (pintype "bidirectional"))
      (node (ref "R8") (pin "2") (pinfunction "2_2") (pintype "passive"))
    )
    (net (code "41") (name "Net-(IC3-PR0(XT2))") (class "Default")
      (node (ref "IC3") (pin "36") (pinfunction "PR0(XT2)_36") (pintype "bidirectional"))
      (node (ref "JP15") (pin "1") (pinfunction "1_1") (pintype "passive"))
    )
    (net (code "42") (name "Net-(IC3-PR1(XT1))") (class "Default")
      (node (ref "IC3") (pin "37") (pinfunction "PR1(XT1)_37") (pintype "bidirectional"))
      (node (ref "JP15") (pin "2") (pinfunction "2_2") (pintype "passive"))
    )
    (net (code "43") (name "Net-(IC3-VCC)") (class "Default")
      (node (ref "IC3") (pin "19") (pinfunction "VCC1_19") (pintype "power_in"))
      (node (ref "IC3") (pin "31") (pinfunction "VCC2_31") (pintype "power_in"))
      (node (ref "IC3") (pin "9") (pinfunction "VCC_9") (pintype "power_in"))
      (node (ref "JP12") (pin "1") (pinfunction "1_1") (pintype "passive"))
      (node (ref "R5") (pin "2") (pinfunction "2_2") (pintype "passive"))
    )
    (net (code "44") (name "Net-(IC3-~{RESET}{slash}PDI_CLK)") (class "Default")
      (node (ref "IC3") (pin "35") (pinfunction "~{RESET}/PDI_CLK_35") (pintype "bidirectional"))
      (node (ref "R7") (pin "2") (pinfunction "2_2") (pintype "passive"))
    )
    (net (code "45") (name "Net-(JP16-Pad1)") (class "Default")
      (node (ref "JP16") (pin "1") (pinfunction "1_1") (pintype "passive"))
      (node (ref "JP20") (pin "3") (pinfunction "3_3") (pintype "passive"))
    )
    (net (code "46") (name "Net-(JP16-Pad6)") (class "Default")
      (node (ref "JP16") (pin "6") (pinfunction "6_6") (pintype "passive"))
      (node (ref "JP23") (pin "2") (pinfunction "2_2") (pintype "passive"))
    )
    (net (code "47") (name "Net-(L1-Pad2)") (class "Default")
      (node (ref "L1") (pin "2") (pinfunction "2_2") (pintype "passive"))
      (node (ref "R9") (pin "2") (pinfunction "2_2") (pintype "passive"))
    )
    (net (code "48") (name "Net-(LED1-C)") (class "Default")
      (node (ref "LED1") (pin "K") (pinfunction "C_K") (pintype "passive"))
      (node (ref "R10") (pin "1") (pinfunction "1_1") (pintype "passive"))
    )
    (net (code "49") (name "Net-(Q2-OUT)") (class "Default")
      (node (ref "JP18") (pin "1") (pinfunction "1_1") (pintype "passive"))
      (node (ref "Q2") (pin "3") (pinfunction "OUT_3") (pintype "output"))
    )
    (net (code "50") (name "Net-(Q3-OUT)") (class "Default")
      (node (ref "JP18") (pin "3") (pinfunction "3_3") (pintype "passive"))
      (node (ref "Q3") (pin "3") (pinfunction "OUT_3") (pintype "output"))
    )
    (net (code "51") (name "Net-(U1-IN)") (class "Default")
      (node (ref "C19") (pin "2") (pinfunction "2_2") (pintype "passive"))
      (node (ref "U1") (pin "6") (pinfunction "IN_6") (pintype "bidirectional"))
    )
    (net (code "52") (name "Net-(U1-OUT)") (class "Default")
      (node (ref "C21") (pin "1") (pinfunction "1_1") (pintype "passive"))
      (node (ref "U1") (pin "3") (pinfunction "OUT_3") (pintype "bidirectional"))
    )
    (net (code "53") (name "Net-(U2-IN)") (class "Default")
      (node (ref "C20") (pin "2") (pinfunction "2_2") (pintype "passive"))
      (node (ref "U2") (pin "6") (pinfunction "IN_6") (pintype "bidirectional"))
    )
    (net (code "54") (name "Net-(U2-OUT)") (class "Default")
      (node (ref "C22") (pin "1") (pinfunction "1_1") (pintype "passive"))
      (node (ref "U2") (pin "3") (pinfunction "OUT_3") (pintype "bidirectional"))
    )
    (net (code "55") (name "OSCOUT") (class "Default")
      (node (ref "JP17") (pin "1") (pinfunction "1_1") (pintype "passive"))
      (node (ref "JP18") (pin "2") (pinfunction "2_2") (pintype "passive"))
      (node (ref "JP18") (pin "4") (pinfunction "4_4") (pintype "passive"))
      (node (ref "JP18") (pin "6") (pinfunction "6_6") (pintype "passive"))
      (node (ref "JP4") (pin "1") (pinfunction "1_1") (pintype "passive"))
    )
    (net (code "56") (name "PDIC") (class "Default")
      (node (ref "JP9") (pin "13") (pinfunction "13_13") (pintype "passive"))
      (node (ref "R7") (pin "1") (pinfunction "1_1") (pintype "passive"))
    )
    (net (code "57") (name "PDID") (class "Default")
      (node (ref "JP9") (pin "15") (pinfunction "15_15") (pintype "passive"))
      (node (ref "R8") (pin "1") (pinfunction "1_1") (pintype "passive"))
    )
    (net (code "58") (name "RESET") (class "Default")
      (node (ref "IC1") (pin "1") (pinfunction "PC6(/RESET/PCINT14)_1") (pintype "bidirectional"))
      (node (ref "JP8") (pin "6") (pinfunction "6_6") (pintype "passive"))
      (node (ref "JP9") (pin "5") (pinfunction "5_5") (pintype "passive"))
      (node (ref "R11") (pin "1") (pinfunction "1_1") (pintype "passive"))
    )
    (net (code "59") (name "RXD") (class "Default")
      (node (ref "JP11") (pin "2") (pinfunction "2_2") (pintype "passive"))
      (node (ref "JP23") (pin "3") (pinfunction "3_3") (pintype "passive"))
      (node (ref "JP5") (pin "2") (pinfunction "2_2") (pintype "passive"))
      (node (ref "JP9") (pin "10") (pinfunction "10_10") (pintype "passive"))
    )
    (net (code "60") (name "SCK") (class "Default")
      (node (ref "IC1") (pin "19") (pinfunction "PB5(SCK/PCINT5)_19") (pintype "bidirectional"))
      (node (ref "JP8") (pin "4") (pinfunction "4_4") (pintype "passive"))
      (node (ref "JP9") (pin "11") (pinfunction "11_11") (pintype "passive"))
    )
    (net (code "61") (name "TRIG") (class "Default")
      (node (ref "JP13") (pin "2") (pinfunction "2_2") (pintype "passive"))
      (node (ref "JP22") (pin "2") (pinfunction "2_2") (pintype "passive"))
      (node (ref "JP24") (pin "1") (pinfunction "1_1") (pintype "passive"))
      (node (ref "JP28") (pin "1") (pinfunction "1_1") (pintype "passive"))
      (node (ref "JP9") (pin "16") (pinfunction "16_16") (pintype "passive"))
    )
    (net (code "62") (name "TXD") (class "Default")
      (node (ref "JP10") (pin "1") (pinfunction "1_1") (pintype "passive"))
      (node (ref "JP6") (pin "1") (pinfunction "1_1") (pintype "passive"))
      (node (ref "JP9") (pin "12") (pinfunction "12_12") (pintype "passive"))
    )
    (net (code "63") (name "VCCIO") (class "Default")
      (node (ref "C1") (pin "1") (pinfunction "1_1") (pintype "passive"))
      (node (ref "C2") (pin "1") (pinfunction "1_1") (pintype "passive"))
      (node (ref "C27") (pin "1") (pinfunction "1_1") (pintype "passive"))
      (node (ref "C28") (pin "1") (pinfunction "1_1") (pintype "passive"))
      (node (ref "C3") (pin "1") (pinfunction "1_1") (pintype "passive"))
      (node (ref "C30") (pin "+") (pinfunction "+_+") (pintype "passive"))
      (node (ref "C4") (pin "1") (pinfunction "1_1") (pintype "passive"))
      (node (ref "IC1") (pin "20") (pinfunction "AVCC_20") (pintype "passive"))
      (node (ref "IC1") (pin "21") (pinfunction "AREF_21") (pintype "passive"))
      (node (ref "JP1") (pin "6") (pinfunction "6_6") (pintype "passive"))
      (node (ref "JP14") (pin "2") (pinfunction "2_2") (pintype "passive"))
      (node (ref "JP20") (pin "1") (pinfunction "1_1") (pintype "passive"))
      (node (ref "R1") (pin "1") (pinfunction "1_1") (pintype "passive"))
      (node (ref "R9") (pin "1") (pinfunction "1_1") (pintype "passive"))
    )
    (net (code "64") (name "VMON") (class "Default")
      (node (ref "JP1") (pin "3") (pinfunction "3_3") (pintype "passive"))
      (node (ref "JP1") (pin "4") (pinfunction "4_4") (pintype "passive"))
      (node (ref "JP12") (pin "3") (pinfunction "3_3") (pintype "passive"))
      (node (ref "JP12") (pin "4") (pinfunction "4_4") (pintype "passive"))
      (node (ref "JP21") (pin "2") (pinfunction "2_2") (pintype "passive"))
      (node (ref "JP26") (pin "1") (pinfunction "1_1") (pintype "passive"))
      (node (ref "JP7") (pin "3") (pinfunction "3_3") (pintype "passive"))
      (node (ref "JP7") (pin "4") (pinfunction "4_4") (pintype "passive"))
      (node (ref "X4") (pin "1") (pinfunction "1_1") (pintype "passive"))
    )
    (net (code "65") (name "VREF") (class "Default")
      (node (ref "C31") (pin "1") (pinfunction "1_1") (pintype "passive"))
      (node (ref "C8") (pin "1") (pinfunction "1_1") (pintype "passive"))
      (node (ref "C9") (pin "1") (pinfunction "1_1") (pintype "passive"))
      (node (ref "JP20") (pin "2") (pinfunction "2_2") (pintype "passive"))
      (node (ref "JP7") (pin "6") (pinfunction "6_6") (pintype "passive"))
      (node (ref "JP9") (pin "8") (pinfunction "8_8") (pintype "passive"))
      (node (ref "R11") (pin "2") (pinfunction "2_2") (pintype "passive"))
      (node (ref "R12") (pin "2") (pinfunction "2_2") (pintype "passive"))
      (node (ref "R3") (pin "1") (pinfunction "1_1") (pintype "passive"))
    )
    (net (code "66") (name "unconnected-(CON1B-1-PadS1)") (class "Default")
      (node (ref "CON1") (pin "S1") (pinfunction "1_S1") (pintype "passive"))
    )
    (net (code "67") (name "unconnected-(CON1B-2-PadS2)") (class "Default")
      (node (ref "CON1") (pin "S2") (pinfunction "2_S2") (pintype "passive"))
    )
    (net (code "68") (name "unconnected-(IC1-PB1(OC1A{slash}PCINT1)-Pad15)") (class "Default")
      (node (ref "IC1") (pin "15") (pinfunction "PB1(OC1A/PCINT1)_15") (pintype "bidirectional"))
    )
    (net (code "69") (name "unconnected-(IC1-PB2(SS{slash}OC1B{slash}PCINT2)-Pad16)") (class "Default")
      (node (ref "IC1") (pin "16") (pinfunction "PB2(SS/OC1B/PCINT2)_16") (pintype "bidirectional"))
    )
    (net (code "70") (name "unconnected-(IC1-PD2(INT0{slash}PCINT18)-Pad4)") (class "Default")
      (node (ref "IC1") (pin "4") (pinfunction "PD2(INT0/PCINT18)_4") (pintype "bidirectional"))
    )
    (net (code "71") (name "unconnected-(IC1-PD3(INT1{slash}OC2B{slash}PCINT19)-Pad5)") (class "Default")
      (node (ref "IC1") (pin "5") (pinfunction "PD3(INT1/OC2B/PCINT19)_5") (pintype "bidirectional"))
    )
    (net (code "72") (name "unconnected-(IC1-PD4(T0{slash}XCK{slash}PCINT20)-Pad6)") (class "Default")
      (node (ref "IC1") (pin "6") (pinfunction "PD4(T0/XCK/PCINT20)_6") (pintype "bidirectional"))
    )
    (net (code "73") (name "unconnected-(IC1-PD5(T1{slash}OC0B{slash}PCINT21)-Pad11)") (class "Default")
      (node (ref "IC1") (pin "11") (pinfunction "PD5(T1/OC0B/PCINT21)_11") (pintype "bidirectional"))
    )
    (net (code "74") (name "unconnected-(IC1-PD6(AIN0{slash}OC0A{slash}PCINT22)-Pad12)") (class "Default")
      (node (ref "IC1") (pin "12") (pinfunction "PD6(AIN0/OC0A/PCINT22)_12") (pintype "bidirectional"))
    )
    (net (code "75") (name "unconnected-(IC1-PD7(AIN1{slash}PCINT23)-Pad13)") (class "Default")
      (node (ref "IC1") (pin "13") (pinfunction "PD7(AIN1/PCINT23)_13") (pintype "bidirectional"))
    )
    (net (code "76") (name "unconnected-(IC2-Pad2)") (class "Default")
      (node (ref "IC2") (pin "2") (pinfunction "2_2") (pintype "passive"))
    )
    (net (code "77") (name "unconnected-(IC2-Pad3)") (class "Default")
      (node (ref "IC2") (pin "3") (pinfunction "3_3") (pintype "passive"))
    )
    (net (code "78") (name "unconnected-(IC2-Pad5)") (class "Default")
      (node (ref "IC2") (pin "5") (pinfunction "5_5") (pintype "passive"))
    )
    (net (code "79") (name "unconnected-(IC2-Pad6)") (class "Default")
      (node (ref "IC2") (pin "6") (pinfunction "6_6") (pintype "passive"))
    )
    (net (code "80") (name "unconnected-(IC2-Pad9)") (class "Default")
      (node (ref "IC2") (pin "9") (pinfunction "9_9") (pintype "passive"))
    )
    (net (code "81") (name "unconnected-(IC2-Pad10)") (class "Default")
      (node (ref "IC2") (pin "10") (pinfunction "10_10") (pintype "passive"))
    )
    (net (code "82") (name "unconnected-(IC2-Pad12)") (class "Default")
      (node (ref "IC2") (pin "12") (pinfunction "12_12") (pintype "passive"))
    )
    (net (code "83") (name "unconnected-(IC2-Pad13)") (class "Default")
      (node (ref "IC2") (pin "13") (pinfunction "13_13") (pintype "passive"))
    )
    (net (code "84") (name "unconnected-(IC3-PA1-Pad41)") (class "Default")
      (node (ref "IC3") (pin "41") (pinfunction "PA1_41") (pintype "bidirectional"))
    )
    (net (code "85") (name "unconnected-(IC3-PA2-Pad42)") (class "Default")
      (node (ref "IC3") (pin "42") (pinfunction "PA2_42") (pintype "bidirectional"))
    )
    (net (code "86") (name "unconnected-(IC3-PA3-Pad43)") (class "Default")
      (node (ref "IC3") (pin "43") (pinfunction "PA3_43") (pintype "bidirectional"))
    )
    (net (code "87") (name "unconnected-(IC3-PA4-Pad44)") (class "Default")
      (node (ref "IC3") (pin "44") (pinfunction "PA4_44") (pintype "bidirectional"))
    )
    (net (code "88") (name "unconnected-(IC3-PA5-Pad1)") (class "Default")
      (node (ref "IC3") (pin "1") (pinfunction "PA5_1") (pintype "bidirectional"))
    )
    (net (code "89") (name "unconnected-(IC3-PA6-Pad2)") (class "Default")
      (node (ref "IC3") (pin "2") (pinfunction "PA6_2") (pintype "bidirectional"))
    )
    (net (code "90") (name "unconnected-(IC3-PA7-Pad3)") (class "Default")
      (node (ref "IC3") (pin "3") (pinfunction "PA7_3") (pintype "bidirectional"))
    )
    (net (code "91") (name "unconnected-(IC3-PB0-Pad4)") (class "Default")
      (node (ref "IC3") (pin "4") (pinfunction "PB0_4") (pintype "bidirectional"))
    )
    (net (code "92") (name "unconnected-(IC3-PB1-Pad5)") (class "Default")
      (node (ref "IC3") (pin "5") (pinfunction "PB1_5") (pintype "bidirectional"))
    )
    (net (code "93") (name "unconnected-(IC3-PB2-Pad6)") (class "Default")
      (node (ref "IC3") (pin "6") (pinfunction "PB2_6") (pintype "bidirectional"))
    )
    (net (code "94") (name "unconnected-(IC3-PB3-Pad7)") (class "Default")
      (node (ref "IC3") (pin "7") (pinfunction "PB3_7") (pintype "bidirectional"))
    )
    (net (code "95") (name "unconnected-(IC3-PC0-Pad10)") (class "Default")
      (node (ref "IC3") (pin "10") (pinfunction "PC0_10") (pintype "bidirectional"))
    )
    (net (code "96") (name "unconnected-(IC3-PC1-Pad11)") (class "Default")
      (node (ref "IC3") (pin "11") (pinfunction "PC1_11") (pintype "bidirectional"))
    )
    (net (code "97") (name "unconnected-(IC3-PC4-Pad14)") (class "Default")
      (node (ref "IC3") (pin "14") (pinfunction "PC4_14") (pintype "bidirectional"))
    )
    (net (code "98") (name "unconnected-(IC3-PC5-Pad15)") (class "Default")
      (node (ref "IC3") (pin "15") (pinfunction "PC5_15") (pintype "bidirectional"))
    )
    (net (code "99") (name "unconnected-(IC3-PC6-Pad16)") (class "Default")
      (node (ref "IC3") (pin "16") (pinfunction "PC6_16") (pintype "bidirectional"))
    )
    (net (code "100") (name "unconnected-(IC3-PC7-Pad17)") (class "Default")
      (node (ref "IC3") (pin "17") (pinfunction "PC7_17") (pintype "bidirectional"))
    )
    (net (code "101") (name "unconnected-(IC3-PD0-Pad20)") (class "Default")
      (node (ref "IC3") (pin "20") (pinfunction "PD0_20") (pintype "bidirectional"))
    )
    (net (code "102") (name "unconnected-(IC3-PD1-Pad21)") (class "Default")
      (node (ref "IC3") (pin "21") (pinfunction "PD1_21") (pintype "bidirectional"))
    )
    (net (code "103") (name "unconnected-(IC3-PD2-Pad22)") (class "Default")
      (node (ref "IC3") (pin "22") (pinfunction "PD2_22") (pintype "bidirectional"))
    )
    (net (code "104") (name "unconnected-(IC3-PD3-Pad23)") (class "Default")
      (node (ref "IC3") (pin "23") (pinfunction "PD3_23") (pintype "bidirectional"))
    )
    (net (code "105") (name "unconnected-(IC3-PD4-Pad24)") (class "Default")
      (node (ref "IC3") (pin "24") (pinfunction "PD4_24") (pintype "bidirectional"))
    )
    (net (code "106") (name "unconnected-(IC3-PD5-Pad25)") (class "Default")
      (node (ref "IC3") (pin "25") (pinfunction "PD5_25") (pintype "bidirectional"))
    )
    (net (code "107") (name "unconnected-(IC3-PD6-Pad26)") (class "Default")
      (node (ref "IC3") (pin "26") (pinfunction "PD6_26") (pintype "bidirectional"))
    )
    (net (code "108") (name "unconnected-(IC3-PE0-Pad28)") (class "Default")
      (node (ref "IC3") (pin "28") (pinfunction "PE0_28") (pintype "bidirectional"))
    )
    (net (code "109") (name "unconnected-(IC3-PE1-Pad29)") (class "Default")
      (node (ref "IC3") (pin "29") (pinfunction "PE1_29") (pintype "bidirectional"))
    )
    (net (code "110") (name "unconnected-(IC3-PE2-Pad32)") (class "Default")
      (node (ref "IC3") (pin "32") (pinfunction "PE2_32") (pintype "bidirectional"))
    )
    (net (code "111") (name "unconnected-(IC3-PE3-Pad33)") (class "Default")
      (node (ref "IC3") (pin "33") (pinfunction "PE3_33") (pintype "bidirectional"))
    )
    (net (code "112") (name "unconnected-(JP9-Pad1)") (class "Default")
      (node (ref "JP9") (pin "1") (pinfunction "1_1") (pintype "passive"))
    )
    (net (code "113") (name "unconnected-(JP9-Pad20)") (class "Default")
      (node (ref "JP9") (pin "20") (pinfunction "20_20") (pintype "passive"))
    )
  )
)
